# W25Q128.net
KiCad netlist of a schematic drawn in Altium Designer
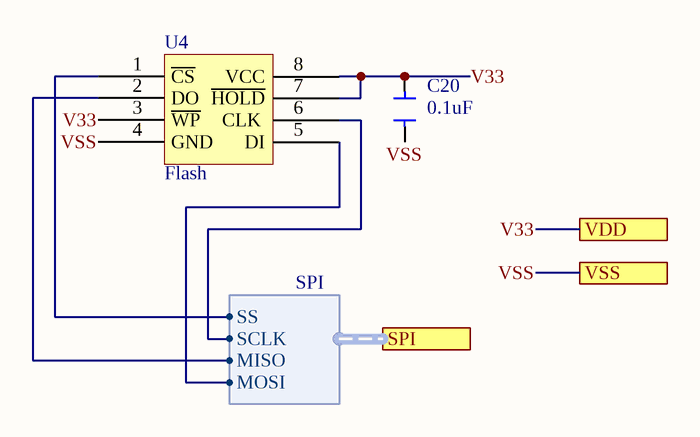
[diagram p0: W25Q128.SchDoc]

(export (version "E")
  (design (tool "Eeschema 10.0.6"))
  (components
    (comp (ref "C20")
      (value "0.1uF")
      (footprint "CAP_0402")
      (fields (field (name "Comment") "Cap"))
      (libsource (lib "ZGR") (part "Cap"))
    )
    (comp (ref "U4") (value "Flash") (footprint "8-Pin SOIC 208-mil") (libsource (lib "ZGR") (part "W25QXX")))
  )
  (nets
    (net (code "2") (name "/MISO") (class "Default")
      (node (ref "U4") (pin "2") (pinfunction "DO_2") (pintype "passive"))
    )
    (net (code "3") (name "/MOSI") (class "Default")
      (node (ref "U4") (pin "5") (pinfunction "DI_5") (pintype "passive"))
    )
    (net (code "4") (name "/SCLK") (class "Default")
      (node (ref "U4") (pin "6") (pinfunction "CLK_6") (pintype "passive"))
    )
    (net (code "5") (name "/SS") (class "Default")
      (node (ref "U4") (pin "1") (pinfunction "~{CS}_1") (pintype "passive"))
    )
    (net (code "6") (name "/V33") (class "Default")
      (node (ref "C20") (pin "1") (pinfunction "1_1") (pintype "passive"))
      (node (ref "U4") (pin "3") (pinfunction "~{WP}_3") (pintype "passive"))
      (node (ref "U4") (pin "7") (pinfunction "~{HOLD}_7") (pintype "passive"))
      (node (ref "U4") (pin "8") (pinfunction "VCC_8") (pintype "passive"))
    )
    (net (code "7") (name "/VSS") (class "Default")
      (node (ref "C20") (pin "2") (pinfunction "2_2") (pintype "passive"))
      (node (ref "U4") (pin "4") (pinfunction "GND_4") (pintype "passive"))
    )
  )
)
